# STM32G474CBT6.net
KiCad netlist of a schematic drawn in Altium Designer
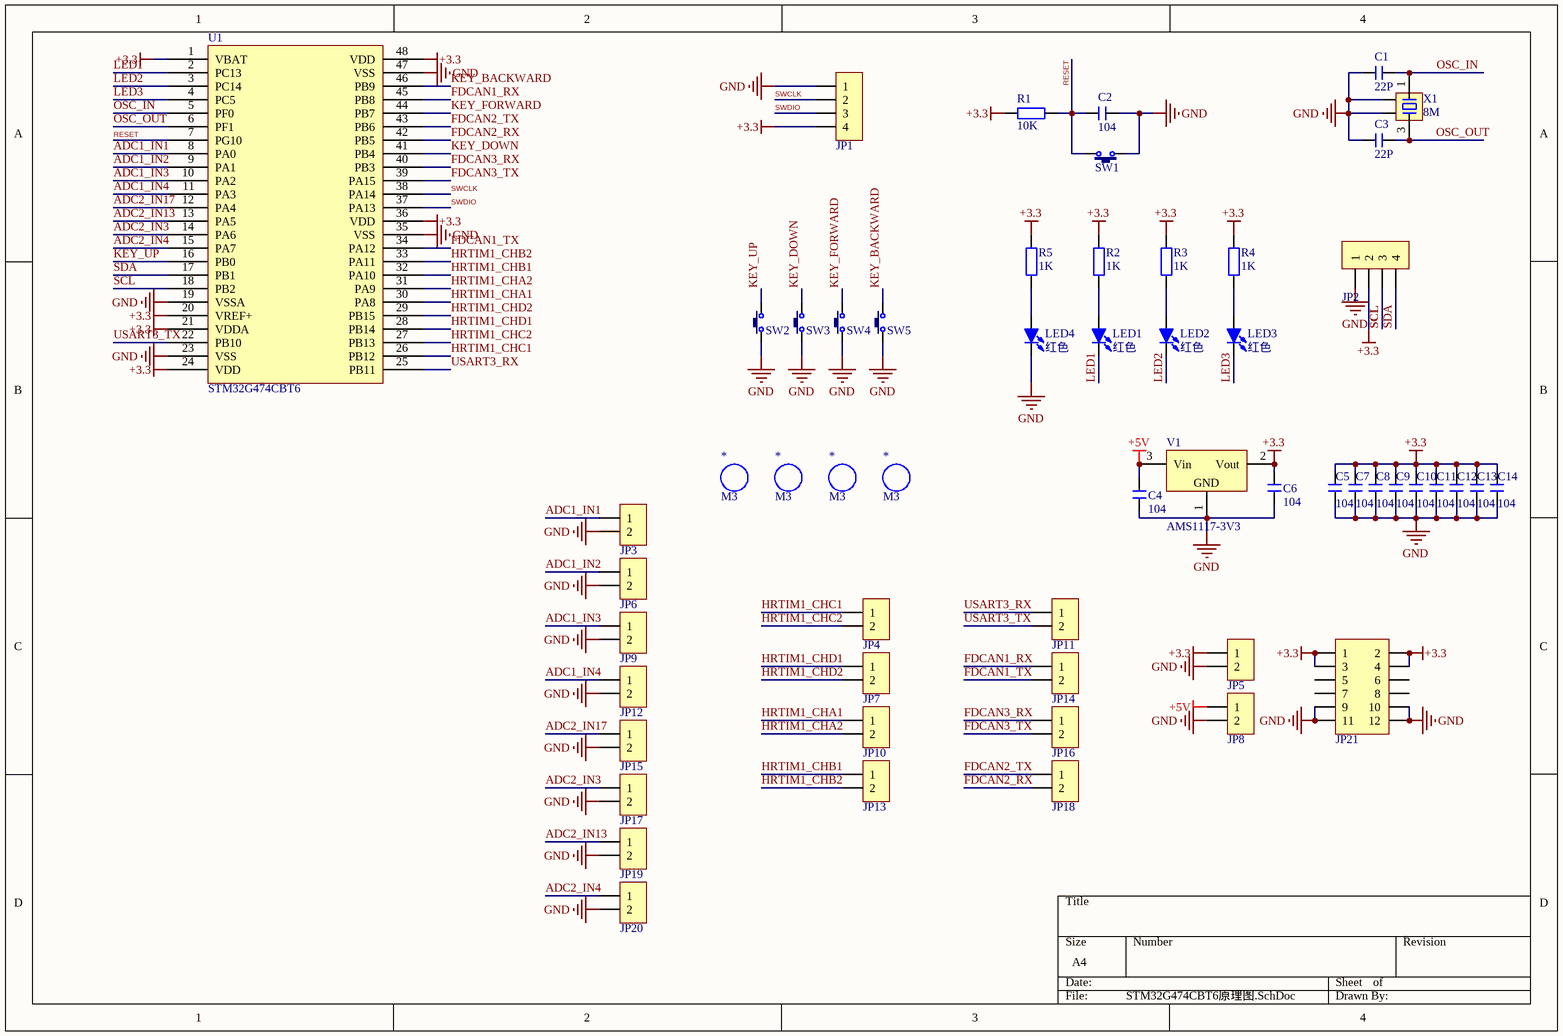
[diagram p0: STM32G474CBT6原理图.SchDoc]

(export (version "E")
  (design (tool "Eeschema 10.0.6"))
  (components
    (comp (ref "C1")
      (value "22P")
      (footprint "C 0603")
      (description "无极性贴片电容")
      (fields (field (name "版权归属") "源创客"))
      (libsource (lib "CKY") (part "C"))
    )
    (comp (ref "C2")
      (value "104")
      (footprint "C 0603")
      (description "直插瓷片电容")
      (fields (field (name "版权归属") "源创客"))
      (libsource (lib "3D库") (part "C-CC"))
    )
    (comp (ref "C3")
      (value "22P")
      (footprint "C 0603")
      (description "无极性贴片电容")
      (fields (field (name "版权归属") "源创客"))
      (libsource (lib "CKY") (part "C"))
    )
    (comp (ref "C4")
      (value "104")
      (footprint "C 0603")
      (description "无极性贴片电容")
      (fields (field (name "版权归属") "源创客"))
      (libsource (lib "CKY") (part "C"))
    )
    (comp (ref "C5")
      (value "104")
      (footprint "C 0402")
      (description "无极性贴片电容")
      (fields (field (name "版权归属") "源创客"))
      (libsource (lib "CKY") (part "C"))
    )
    (comp (ref "C6")
      (value "104")
      (footprint "C 0603")
      (description "无极性贴片电容")
      (fields (field (name "版权归属") "源创客"))
      (libsource (lib "CKY") (part "C"))
    )
    (comp (ref "C7")
      (value "104")
      (footprint "C 0402")
      (description "无极性贴片电容")
      (fields (field (name "版权归属") "源创客"))
      (libsource (lib "CKY") (part "C"))
    )
    (comp (ref "C8")
      (value "104")
      (footprint "C 0402")
      (description "无极性贴片电容")
      (fields (field (name "版权归属") "源创客"))
      (libsource (lib "CKY") (part "C"))
    )
    (comp (ref "C9")
      (value "104")
      (footprint "C 0402")
      (description "无极性贴片电容")
      (fields (field (name "版权归属") "源创客"))
      (libsource (lib "CKY") (part "C"))
    )
    (comp (ref "C10")
      (value "104")
      (footprint "C 0402")
      (description "无极性贴片电容")
      (fields (field (name "版权归属") "源创客"))
      (libsource (lib "CKY") (part "C"))
    )
    (comp (ref "C11")
      (value "104")
      (footprint "C 0402")
      (description "无极性贴片电容")
      (fields (field (name "版权归属") "源创客"))
      (libsource (lib "CKY") (part "C"))
    )
    (comp (ref "C12")
      (value "104")
      (footprint "C 0402")
      (description "无极性贴片电容")
      (fields (field (name "版权归属") "源创客"))
      (libsource (lib "CKY") (part "C"))
    )
    (comp (ref "C13")
      (value "104")
      (footprint "C 0402")
      (description "无极性贴片电容")
      (fields (field (name "版权归属") "源创客"))
      (libsource (lib "CKY") (part "C"))
    )
    (comp (ref "C14")
      (value "104")
      (footprint "C 0402")
      (description "无极性贴片电容")
      (fields (field (name "版权归属") "源创客"))
      (libsource (lib "CKY") (part "C"))
    )
    (comp (ref "JP1")
      (value "HDR-1X4")
      (footprint "XH2.54-4P")
      (description "4P接插件")
      (fields (field (name "版权归属") "源创客"))
      (libsource (lib "3D库") (part "Header 4"))
    )
    (comp (ref "JP2")
      (value "HDR-1X4")
      (footprint "HDR-1X4")
      (description "4P接插件")
      (fields (field (name "版权归属") "源创客"))
      (libsource (lib "CKY") (part "Header 4"))
    )
    (comp (ref "JP3")
      (value "HDR-1X2")
      (footprint "XH2.54-2P")
      (description "2P接插件")
      (fields (field (name "版权归属") "源创客"))
      (libsource (lib "CKY") (part "Header 2"))
    )
    (comp (ref "JP4")
      (value "HDR-1X2")
      (footprint "XH2.54-2P")
      (description "2P接插件")
      (fields (field (name "版权归属") "源创客"))
      (libsource (lib "CKY") (part "Header 2"))
    )
    (comp (ref "JP5")
      (value "HDR-1X2")
      (footprint "XH2.54-2P")
      (description "2P接插件")
      (fields (field (name "版权归属") "源创客"))
      (libsource (lib "CKY") (part "Header 2"))
    )
    (comp (ref "JP6")
      (value "HDR-1X2")
      (footprint "XH2.54-2P")
      (description "2P接插件")
      (fields (field (name "版权归属") "源创客"))
      (libsource (lib "CKY") (part "Header 2"))
    )
    (comp (ref "JP7")
      (value "HDR-1X2")
      (footprint "XH2.54-2P")
      (description "2P接插件")
      (fields (field (name "版权归属") "源创客"))
      (libsource (lib "CKY") (part "Header 2"))
    )
    (comp (ref "JP8")
      (value "HDR-1X2")
      (footprint "XH2.54-2P")
      (description "2P接插件")
      (fields (field (name "版权归属") "源创客"))
      (libsource (lib "CKY") (part "Header 2"))
    )
    (comp (ref "JP9")
      (value "HDR-1X2")
      (footprint "XH2.54-2P")
      (description "2P接插件")
      (fields (field (name "版权归属") "源创客"))
      (libsource (lib "CKY") (part "Header 2"))
    )
    (comp (ref "JP10")
      (value "HDR-1X2")
      (footprint "XH2.54-2P")
      (description "2P接插件")
      (fields (field (name "版权归属") "源创客"))
      (libsource (lib "CKY") (part "Header 2"))
    )
    (comp (ref "JP11")
      (value "HDR-1X2")
      (footprint "XH2.54-2P")
      (description "2P接插件")
      (fields (field (name "版权归属") "源创客"))
      (libsource (lib "CKY") (part "Header 2"))
    )
    (comp (ref "JP12")
      (value "HDR-1X2")
      (footprint "XH2.54-2P")
      (description "2P接插件")
      (fields (field (name "版权归属") "源创客"))
      (libsource (lib "CKY") (part "Header 2"))
    )
    (comp (ref "JP13")
      (value "HDR-1X2")
      (footprint "XH2.54-2P")
      (description "2P接插件")
      (fields (field (name "版权归属") "源创客"))
      (libsource (lib "CKY") (part "Header 2"))
    )
    (comp (ref "JP14")
      (value "HDR-1X2")
      (footprint "XH2.54-2P")
      (description "2P接插件")
      (fields (field (name "版权归属") "源创客"))
      (libsource (lib "CKY") (part "Header 2"))
    )
    (comp (ref "JP15")
      (value "HDR-1X2")
      (footprint "XH2.54-2P")
      (description "2P接插件")
      (fields (field (name "版权归属") "源创客"))
      (libsource (lib "CKY") (part "Header 2"))
    )
    (comp (ref "JP16")
      (value "HDR-1X2")
      (footprint "XH2.54-2P")
      (description "2P接插件")
      (fields (field (name "版权归属") "源创客"))
      (libsource (lib "CKY") (part "Header 2"))
    )
    (comp (ref "JP17")
      (value "HDR-1X2")
      (footprint "XH2.54-2P")
      (description "2P接插件")
      (fields (field (name "版权归属") "源创客"))
      (libsource (lib "CKY") (part "Header 2"))
    )
    (comp (ref "JP18")
      (value "HDR-1X2")
      (footprint "XH2.54-2P")
      (description "2P接插件")
      (fields (field (name "版权归属") "源创客"))
      (libsource (lib "CKY") (part "Header 2"))
    )
    (comp (ref "JP19")
      (value "HDR-1X2")
      (footprint "XH2.54-2P")
      (description "2P接插件")
      (fields (field (name "版权归属") "源创客"))
      (libsource (lib "CKY") (part "Header 2"))
    )
    (comp (ref "JP20")
      (value "HDR-1X2")
      (footprint "XH2.54-2P")
      (description "2P接插件")
      (fields (field (name "版权归属") "源创客"))
      (libsource (lib "CKY") (part "Header 2"))
    )
    (comp (ref "JP21")
      (value "Header 6X2")
      (footprint "HDR-6X2")
      (description "6*2P接插件")
      (fields (field (name "版权归属") "源创客"))
      (libsource (lib "CKY") (part "Header  6X2"))
    )
    (comp (ref "LED1")
      (value "红色")
      (footprint "LED 0603B")
      (description "贴片LED")
      (fields (field (name "版权归属") "源创客"))
      (libsource (lib "CKY") (part "LED-SMD"))
    )
    (comp (ref "LED2")
      (value "红色")
      (footprint "LED 0603B")
      (description "贴片LED")
      (fields (field (name "版权归属") "源创客"))
      (libsource (lib "CKY") (part "LED-SMD"))
    )
    (comp (ref "LED3")
      (value "红色")
      (footprint "LED 0603B")
      (description "贴片LED")
      (fields (field (name "版权归属") "源创客"))
      (libsource (lib "CKY") (part "LED-SMD"))
    )
    (comp (ref "LED4")
      (value "红色")
      (footprint "LED 0603B")
      (description "贴片LED")
      (fields (field (name "版权归属") "源创客"))
      (libsource (lib "CKY") (part "LED-SMD"))
    )
    (comp (ref "R1")
      (value "10K")
      (footprint "R 0603")
      (description "直插色环电阻")
      (fields (field (name "版权归属") "源创客"))
      (libsource (lib "3D库") (part "R-CRR"))
    )
    (comp (ref "R2")
      (value "1K")
      (footprint "R 0603")
      (description "贴片电阻")
      (fields (field (name "版权归属") "源创客"))
      (libsource (lib "CKY") (part "R"))
    )
    (comp (ref "R3")
      (value "1K")
      (footprint "R 0603")
      (description "贴片电阻")
      (fields (field (name "版权归属") "源创客"))
      (libsource (lib "CKY") (part "R"))
    )
    (comp (ref "R4")
      (value "1K")
      (footprint "R 0603")
      (description "贴片电阻")
      (fields (field (name "版权归属") "源创客"))
      (libsource (lib "CKY") (part "R"))
    )
    (comp (ref "R5")
      (value "1K")
      (footprint "R 0603")
      (description "贴片电阻")
      (fields (field (name "版权归属") "源创客"))
      (libsource (lib "CKY") (part "R"))
    )
    (comp (ref "SW1")
      (value "3x6x5")
      (footprint "无声微动开关")
      (description "3x6轻触开关")
      (fields (field (name "版权归属") "源创客"))
      (libsource (lib "") (part "TSW 3x6_1"))
    )
    (comp (ref "SW2")
      (value "3x6x5")
      (footprint "无声微动开关")
      (description "3x6轻触开关")
      (fields (field (name "版权归属") "源创客"))
      (libsource (lib "按键-开关") (part "TSW 3x6"))
    )
    (comp (ref "SW3")
      (value "3x6x5")
      (footprint "无声微动开关")
      (description "3x6轻触开关")
      (fields (field (name "版权归属") "源创客"))
      (libsource (lib "按键-开关") (part "TSW 3x6"))
    )
    (comp (ref "SW4")
      (value "3x6x5")
      (footprint "无声微动开关")
      (description "3x6轻触开关")
      (fields (field (name "版权归属") "源创客"))
      (libsource (lib "按键-开关") (part "TSW 3x6"))
    )
    (comp (ref "SW5")
      (value "3x6x5")
      (footprint "无声微动开关")
      (description "3x6轻触开关")
      (fields (field (name "版权归属") "源创客"))
      (libsource (lib "按键-开关") (part "TSW 3x6"))
    )
    (comp (ref "U1")
      (value "STM32G474CBT6")
      (footprint "LQFP48 7X7_L")
      (libsource (lib "STM32系列单片机") (part "STM32G474CBT6"))
    )
    (comp (ref "V1")
      (value "AMS1117-3V3")
      (footprint "SOT89_M")
      (description "三端稳压芯片")
      (fields (field (name "版权归属") "源创客"))
      (libsource (lib "CKY") (part "AMS1117"))
    )
    (comp (ref "X1")
      (value "8M")
      (footprint "XTAL-3225")
      (description "4脚晶振")
      (fields (field (name "版权归属") "源创客"))
      (libsource (lib "CKY") (part "XTAL-4"))
    )
  )
  (nets
    (net (code "1") (name "+3.3") (class "Default")
      (node (ref "C10") (pin "2") (pinfunction "2_2") (pintype "passive"))
      (node (ref "C11") (pin "2") (pinfunction "2_2") (pintype "passive"))
      (node (ref "C12") (pin "2") (pinfunction "2_2") (pintype "passive"))
      (node (ref "C13") (pin "2") (pinfunction "2_2") (pintype "passive"))
      (node (ref "C14") (pin "2") (pinfunction "2_2") (pintype "passive"))
      (node (ref "C5") (pin "2") (pinfunction "2_2") (pintype "passive"))
      (node (ref "C6") (pin "2") (pinfunction "2_2") (pintype "passive"))
      (node (ref "C7") (pin "2") (pinfunction "2_2") (pintype "passive"))
      (node (ref "C8") (pin "2") (pinfunction "2_2") (pintype "passive"))
      (node (ref "C9") (pin "2") (pinfunction "2_2") (pintype "passive"))
      (node (ref "JP1") (pin "4") (pinfunction "4_4") (pintype "passive"))
      (node (ref "JP2") (pin "2") (pinfunction "2_2") (pintype "passive"))
      (node (ref "JP21") (pin "1") (pinfunction "1_1") (pintype "passive"))
      (node (ref "JP21") (pin "2") (pinfunction "2_2") (pintype "passive"))
      (node (ref "JP21") (pin "3") (pinfunction "3_3") (pintype "passive"))
      (node (ref "JP21") (pin "4") (pinfunction "4_4") (pintype "passive"))
      (node (ref "JP5") (pin "1") (pinfunction "1_1") (pintype "passive"))
      (node (ref "R1") (pin "2") (pinfunction "2_2") (pintype "passive"))
      (node (ref "R2") (pin "2") (pinfunction "2_2") (pintype "passive"))
      (node (ref "R3") (pin "2") (pinfunction "2_2") (pintype "passive"))
      (node (ref "R4") (pin "2") (pinfunction "2_2") (pintype "passive"))
      (node (ref "R5") (pin "2") (pinfunction "2_2") (pintype "passive"))
      (node (ref "U1") (pin "1") (pinfunction "VBAT_1") (pintype "passive"))
      (node (ref "U1") (pin "20") (pinfunction "VREF+_20") (pintype "passive"))
      (node (ref "U1") (pin "21") (pinfunction "VDDA_21") (pintype "passive"))
      (node (ref "U1") (pin "24") (pinfunction "VDD_24") (pintype "passive"))
      (node (ref "U1") (pin "36") (pinfunction "VDD_36") (pintype "passive"))
      (node (ref "U1") (pin "48") (pinfunction "VDD_48") (pintype "passive"))
      (node (ref "V1") (pin "2") (pinfunction "Vout_2") (pintype "passive"))
    )
    (net (code "2") (name "+5V") (class "Default")
      (node (ref "C4") (pin "2") (pinfunction "2_2") (pintype "passive"))
      (node (ref "JP8") (pin "1") (pinfunction "1_1") (pintype "passive"))
      (node (ref "V1") (pin "3") (pinfunction "Vin_3") (pintype "passive"))
    )
    (net (code "3") (name "/ADC1_IN1") (class "Default")
      (node (ref "JP3") (pin "1") (pinfunction "1_1") (pintype "passive"))
      (node (ref "U1") (pin "8") (pinfunction "PA0_8") (pintype "passive"))
    )
    (net (code "4") (name "/ADC1_IN2") (class "Default")
      (node (ref "JP6") (pin "1") (pinfunction "1_1") (pintype "passive"))
      (node (ref "U1") (pin "9") (pinfunction "PA1_9") (pintype "passive"))
    )
    (net (code "5") (name "/ADC1_IN3") (class "Default")
      (node (ref "JP9") (pin "1") (pinfunction "1_1") (pintype "passive"))
      (node (ref "U1") (pin "10") (pinfunction "PA2_10") (pintype "passive"))
    )
    (net (code "6") (name "/ADC1_IN4") (class "Default")
      (node (ref "JP12") (pin "1") (pinfunction "1_1") (pintype "passive"))
      (node (ref "U1") (pin "11") (pinfunction "PA3_11") (pintype "passive"))
    )
    (net (code "7") (name "/ADC2_IN3") (class "Default")
      (node (ref "JP17") (pin "1") (pinfunction "1_1") (pintype "passive"))
      (node (ref "U1") (pin "14") (pinfunction "PA6_14") (pintype "passive"))
    )
    (net (code "8") (name "/ADC2_IN4") (class "Default")
      (node (ref "JP20") (pin "1") (pinfunction "1_1") (pintype "passive"))
      (node (ref "U1") (pin "15") (pinfunction "PA7_15") (pintype "passive"))
    )
    (net (code "9") (name "/ADC2_IN13") (class "Default")
      (node (ref "JP19") (pin "1") (pinfunction "1_1") (pintype "passive"))
      (node (ref "U1") (pin "13") (pinfunction "PA5_13") (pintype "passive"))
    )
    (net (code "10") (name "/ADC2_IN17") (class "Default")
      (node (ref "JP15") (pin "1") (pinfunction "1_1") (pintype "passive"))
      (node (ref "U1") (pin "12") (pinfunction "PA4_12") (pintype "passive"))
    )
    (net (code "11") (name "/FDCAN1_RX") (class "Default")
      (node (ref "JP14") (pin "1") (pinfunction "1_1") (pintype "passive"))
      (node (ref "U1") (pin "45") (pinfunction "PB8_45") (pintype "passive"))
    )
    (net (code "12") (name "/FDCAN1_TX") (class "Default")
      (node (ref "JP14") (pin "2") (pinfunction "2_2") (pintype "passive"))
      (node (ref "U1") (pin "34") (pinfunction "PA12_34") (pintype "passive"))
    )
    (net (code "13") (name "/FDCAN2_RX") (class "Default")
      (node (ref "JP18") (pin "2") (pinfunction "2_2") (pintype "passive"))
      (node (ref "U1") (pin "42") (pinfunction "PB5_42") (pintype "passive"))
    )
    (net (code "14") (name "/FDCAN2_TX") (class "Default")
      (node (ref "JP18") (pin "1") (pinfunction "1_1") (pintype "passive"))
      (node (ref "U1") (pin "43") (pinfunction "PB6_43") (pintype "passive"))
    )
    (net (code "15") (name "/FDCAN3_RX") (class "Default")
      (node (ref "JP16") (pin "1") (pinfunction "1_1") (pintype "passive"))
      (node (ref "U1") (pin "40") (pinfunction "PB3_40") (pintype "passive"))
    )
    (net (code "16") (name "/FDCAN3_TX") (class "Default")
      (node (ref "JP16") (pin "2") (pinfunction "2_2") (pintype "passive"))
      (node (ref "U1") (pin "39") (pinfunction "PA15_39") (pintype "passive"))
    )
    (net (code "17") (name "/HRTIM1_CHA1") (class "Default")
      (node (ref "JP10") (pin "1") (pinfunction "1_1") (pintype "passive"))
      (node (ref "U1") (pin "30") (pinfunction "PA8_30") (pintype "passive"))
    )
    (net (code "18") (name "/HRTIM1_CHA2") (class "Default")
      (node (ref "JP10") (pin "2") (pinfunction "2_2") (pintype "passive"))
      (node (ref "U1") (pin "31") (pinfunction "PA9_31") (pintype "passive"))
    )
    (net (code "19") (name "/HRTIM1_CHB1") (class "Default")
      (node (ref "JP13") (pin "1") (pinfunction "1_1") (pintype "passive"))
      (node (ref "U1") (pin "32") (pinfunction "PA10_32") (pintype "passive"))
    )
    (net (code "20") (name "/HRTIM1_CHB2") (class "Default")
      (node (ref "JP13") (pin "2") (pinfunction "2_2") (pintype "passive"))
      (node (ref "U1") (pin "33") (pinfunction "PA11_33") (pintype "passive"))
    )
    (net (code "21") (name "/HRTIM1_CHC1") (class "Default")
      (node (ref "JP4") (pin "1") (pinfunction "1_1") (pintype "passive"))
      (node (ref "U1") (pin "26") (pinfunction "PB12_26") (pintype "passive"))
    )
    (net (code "22") (name "/HRTIM1_CHC2") (class "Default")
      (node (ref "JP4") (pin "2") (pinfunction "2_2") (pintype "passive"))
      (node (ref "U1") (pin "27") (pinfunction "PB13_27") (pintype "passive"))
    )
    (net (code "23") (name "/HRTIM1_CHD1") (class "Default")
      (node (ref "JP7") (pin "1") (pinfunction "1_1") (pintype "passive"))
      (node (ref "U1") (pin "28") (pinfunction "PB14_28") (pintype "passive"))
    )
    (net (code "24") (name "/HRTIM1_CHD2") (class "Default")
      (node (ref "JP7") (pin "2") (pinfunction "2_2") (pintype "passive"))
      (node (ref "U1") (pin "29") (pinfunction "PB15_29") (pintype "passive"))
    )
    (net (code "25") (name "/KEY_BACKWARD") (class "Default")
      (node (ref "SW5") (pin "2") (pinfunction "2_2") (pintype "passive"))
      (node (ref "U1") (pin "46") (pinfunction "PB9_46") (pintype "passive"))
    )
    (net (code "26") (name "/KEY_DOWN") (class "Default")
      (node (ref "SW3") (pin "2") (pinfunction "2_2") (pintype "passive"))
      (node (ref "U1") (pin "41") (pinfunction "PB4_41") (pintype "passive"))
    )
    (net (code "27") (name "/KEY_FORWARD") (class "Default")
      (node (ref "SW4") (pin "2") (pinfunction "2_2") (pintype "passive"))
      (node (ref "U1") (pin "44") (pinfunction "PB7_44") (pintype "passive"))
    )
    (net (code "28") (name "/KEY_UP") (class "Default")
      (node (ref "SW2") (pin "2") (pinfunction "2_2") (pintype "passive"))
      (node (ref "U1") (pin "16") (pinfunction "PB0_16") (pintype "passive"))
    )
    (net (code "29") (name "/LED1") (class "Default")
      (node (ref "LED1") (pin "2") (pinfunction "K_2") (pintype "passive"))
      (node (ref "U1") (pin "2") (pinfunction "PC13_2") (pintype "passive"))
    )
    (net (code "30") (name "/LED2") (class "Default")
      (node (ref "LED2") (pin "2") (pinfunction "K_2") (pintype "passive"))
      (node (ref "U1") (pin "3") (pinfunction "PC14_3") (pintype "passive"))
    )
    (net (code "31") (name "/LED3") (class "Default")
      (node (ref "LED3") (pin "2") (pinfunction "K_2") (pintype "passive"))
      (node (ref "U1") (pin "4") (pinfunction "PC5_4") (pintype "passive"))
    )
    (net (code "32") (name "/OSC_IN") (class "Default")
      (node (ref "C1") (pin "2") (pinfunction "2_2") (pintype "passive"))
      (node (ref "U1") (pin "5") (pinfunction "PF0_5") (pintype "passive"))
      (node (ref "X1") (pin "1") (pinfunction "1_1") (pintype "passive"))
    )
    (net (code "33") (name "/OSC_OUT") (class "Default")
      (node (ref "C3") (pin "2") (pinfunction "2_2") (pintype "passive"))
      (node (ref "U1") (pin "6") (pinfunction "PF1_6") (pintype "passive"))
      (node (ref "X1") (pin "3") (pinfunction "3_3") (pintype "passive"))
    )
    (net (code "34") (name "/RESET") (class "Default")
      (node (ref "C2") (pin "1") (pinfunction "1_1") (pintype "passive"))
      (node (ref "R1") (pin "1") (pinfunction "1_1") (pintype "passive"))
      (node (ref "SW1") (pin "2") (pinfunction "2_2") (pintype "passive"))
      (node (ref "U1") (pin "7") (pinfunction "PG10_7") (pintype "passive"))
    )
    (net (code "35") (name "/SCL") (class "Default")
      (node (ref "JP2") (pin "3") (pinfunction "3_3") (pintype "passive"))
      (node (ref "U1") (pin "18") (pinfunction "PB2_18") (pintype "passive"))
    )
    (net (code "36") (name "/SDA") (class "Default")
      (node (ref "JP2") (pin "4") (pinfunction "4_4") (pintype "passive"))
      (node (ref "U1") (pin "17") (pinfunction "PB1_17") (pintype "passive"))
    )
    (net (code "37") (name "/SWCLK") (class "Default")
      (node (ref "JP1") (pin "2") (pinfunction "2_2") (pintype "passive"))
      (node (ref "U1") (pin "38") (pinfunction "PA14_38") (pintype "passive"))
    )
    (net (code "38") (name "/SWDIO") (class "Default")
      (node (ref "JP1") (pin "3") (pinfunction "3_3") (pintype "passive"))
      (node (ref "U1") (pin "37") (pinfunction "PA13_37") (pintype "passive"))
    )
    (net (code "39") (name "/USART3_RX") (class "Default")
      (node (ref "JP11") (pin "1") (pinfunction "1_1") (pintype "passive"))
      (node (ref "U1") (pin "25") (pinfunction "PB11_25") (pintype "passive"))
    )
    (net (code "40") (name "/USART3_TX") (class "Default")
      (node (ref "JP11") (pin "2") (pinfunction "2_2") (pintype "passive"))
      (node (ref "U1") (pin "22") (pinfunction "PB10_22") (pintype "passive"))
    )
    (net (code "41") (name "GND") (class "Default")
      (node (ref "C1") (pin "1") (pinfunction "1_1") (pintype "passive"))
      (node (ref "C10") (pin "1") (pinfunction "1_1") (pintype "passive"))
      (node (ref "C11") (pin "1") (pinfunction "1_1") (pintype "passive"))
      (node (ref "C12") (pin "1") (pinfunction "1_1") (pintype "passive"))
      (node (ref "C13") (pin "1") (pinfunction "1_1") (pintype "passive"))
      (node (ref "C14") (pin "1") (pinfunction "1_1") (pintype "passive"))
      (node (ref "C2") (pin "2") (pinfunction "2_2") (pintype "passive"))
      (node (ref "C3") (pin "1") (pinfunction "1_1") (pintype "passive"))
      (node (ref "C4") (pin "1") (pinfunction "1_1") (pintype "passive"))
      (node (ref "C5") (pin "1") (pinfunction "1_1") (pintype "passive"))
      (node (ref "C6") (pin "1") (pinfunction "1_1") (pintype "passive"))
      (node (ref "C7") (pin "1") (pinfunction "1_1") (pintype "passive"))
      (node (ref "C8") (pin "1") (pinfunction "1_1") (pintype "passive"))
      (node (ref "C9") (pin "1") (pinfunction "1_1") (pintype "passive"))
      (node (ref "JP1") (pin "1") (pinfunction "1_1") (pintype "passive"))
      (node (ref "JP12") (pin "2") (pinfunction "2_2") (pintype "passive"))
      (node (ref "JP15") (pin "2") (pinfunction "2_2") (pintype "passive"))
      (node (ref "JP17") (pin "2") (pinfunction "2_2") (pintype "passive"))
      (node (ref "JP19") (pin "2") (pinfunction "2_2") (pintype "passive"))
      (node (ref "JP2") (pin "1") (pinfunction "1_1") (pintype "passive"))
      (node (ref "JP20") (pin "2") (pinfunction "2_2") (pintype "passive"))
      (node (ref "JP21") (pin "10") (pinfunction "10_10") (pintype "passive"))
      (node (ref "JP21") (pin "11") (pinfunction "11_11") (pintype "passive"))
      (node (ref "JP21") (pin "12") (pinfunction "12_12") (pintype "passive"))
      (node (ref "JP21") (pin "9") (pinfunction "9_9") (pintype "passive"))
      (node (ref "JP3") (pin "2") (pinfunction "2_2") (pintype "passive"))
      (node (ref "JP5") (pin "2") (pinfunction "2_2") (pintype "passive"))
      (node (ref "JP6") (pin "2") (pinfunction "2_2") (pintype "passive"))
      (node (ref "JP8") (pin "2") (pinfunction "2_2") (pintype "passive"))
      (node (ref "JP9") (pin "2") (pinfunction "2_2") (pintype "passive"))
      (node (ref "LED4") (pin "2") (pinfunction "K_2") (pintype "passive"))
      (node (ref "SW1") (pin "1") (pinfunction "1_1") (pintype "passive"))
      (node (ref "SW2") (pin "1") (pinfunction "1_1") (pintype "passive"))
      (node (ref "SW3") (pin "1") (pinfunction "1_1") (pintype "passive"))
      (node (ref "SW4") (pin "1") (pinfunction "1_1") (pintype "passive"))
      (node (ref "SW5") (pin "1") (pinfunction "1_1") (pintype "passive"))
      (node (ref "U1") (pin "19") (pinfunction "VSSA_19") (pintype "passive"))
      (node (ref "U1") (pin "23") (pinfunction "VSS_23") (pintype "passive"))
      (node (ref "U1") (pin "35") (pinfunction "VSS_35") (pintype "passive"))
      (node (ref "U1") (pin "47") (pinfunction "VSS_47") (pintype "passive"))
      (node (ref "V1") (pin "1") (pinfunction "GND_1") (pintype "passive"))
      (node (ref "X1") (pin "2") (pinfunction "2_2") (pintype "passive"))
      (node (ref "X1") (pin "4") (pinfunction "4_4") (pintype "passive"))
    )
    (net (code "42") (name "Net-(LED1-A)") (class "Default")
      (node (ref "LED1") (pin "1") (pinfunction "A_1") (pintype "passive"))
      (node (ref "R2") (pin "1") (pinfunction "1_1") (pintype "passive"))
    )
    (net (code "43") (name "Net-(LED2-A)") (class "Default")
      (node (ref "LED2") (pin "1") (pinfunction "A_1") (pintype "passive"))
      (node (ref "R3") (pin "1") (pinfunction "1_1") (pintype "passive"))
    )
    (net (code "44") (name "Net-(LED3-A)") (class "Default")
      (node (ref "LED3") (pin "1") (pinfunction "A_1") (pintype "passive"))
      (node (ref "R4") (pin "1") (pinfunction "1_1") (pintype "passive"))
    )
    (net (code "45") (name "Net-(LED4-A)") (class "Default")
      (node (ref "LED4") (pin "1") (pinfunction "A_1") (pintype "passive"))
      (node (ref "R5") (pin "1") (pinfunction "1_1") (pintype "passive"))
    )
    (net (code "46") (name "unconnected-(JP21-Pad5)") (class "Default")
      (node (ref "JP21") (pin "5") (pinfunction "5_5") (pintype "passive"))
    )
    (net (code "47") (name "unconnected-(JP21-Pad6)") (class "Default")
      (node (ref "JP21") (pin "6") (pinfunction "6_6") (pintype "passive"))
    )
    (net (code "48") (name "unconnected-(JP21-Pad7)") (class "Default")
      (node (ref "JP21") (pin "7") (pinfunction "7_7") (pintype "passive"))
    )
    (net (code "49") (name "unconnected-(JP21-Pad8)") (class "Default")
      (node (ref "JP21") (pin "8") (pinfunction "8_8") (pintype "passive"))
    )
  )
)
